# sb-mote.net
KiCad netlist of a schematic drawn in EAGLE
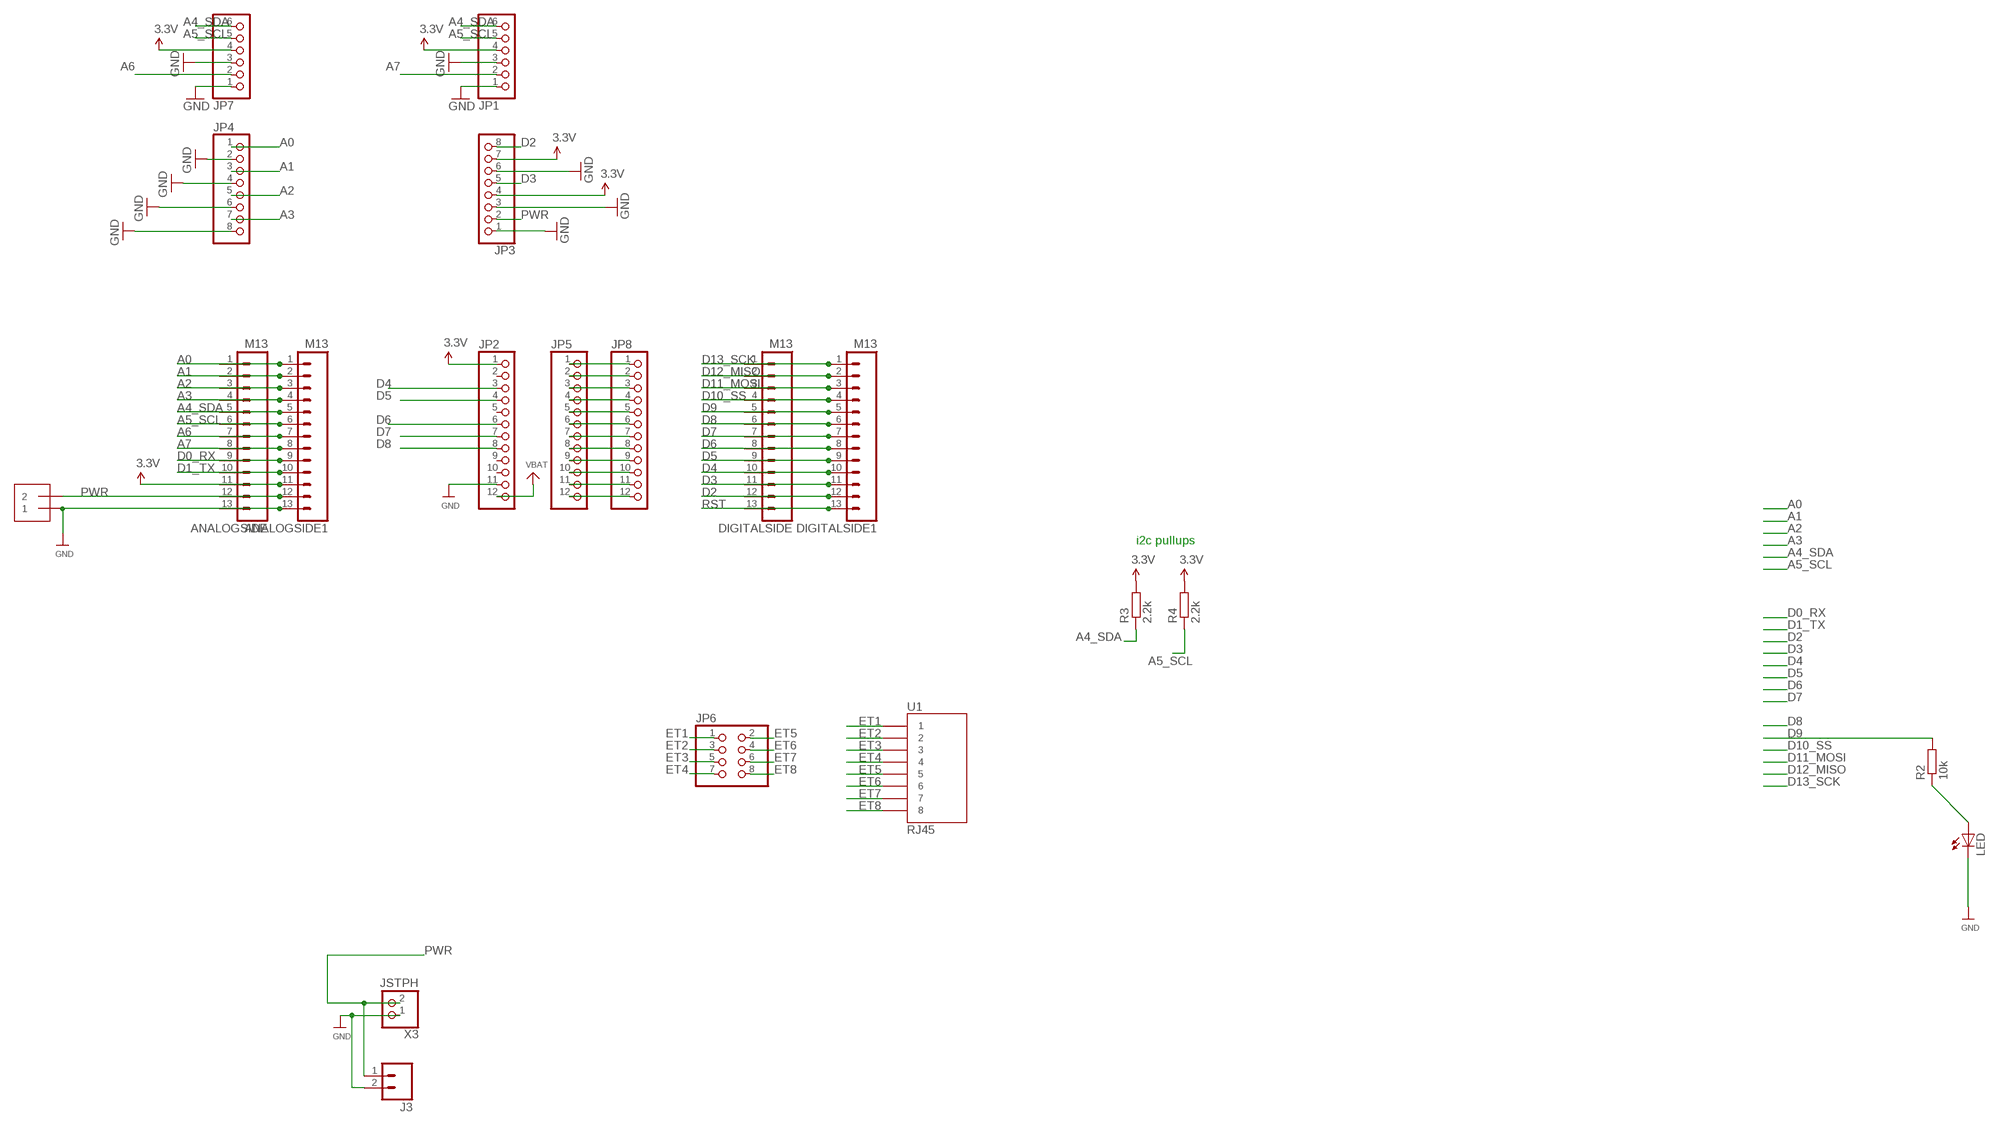
[diagram p0: schematic, sheet 1]

(export (version "E")
  (design (tool "Eeschema 10.0.6"))
  (components
    (comp (ref "ANALOGSIDE")
      (value "M13")
      (footprint "eagle-import:1X13")
      (libsource (lib "eagle-import") (part "M13"))
    )
    (comp (ref "ANALOGSIDE1")
      (value "M13")
      (footprint "eagle-import:1X13")
      (libsource (lib "eagle-import") (part "M13"))
    )
    (comp (ref "DIGITALSIDE")
      (value "M13")
      (footprint "eagle-import:1X13")
      (libsource (lib "eagle-import") (part "M13"))
    )
    (comp (ref "DIGITALSIDE1")
      (value "M13")
      (footprint "eagle-import:1X13")
      (libsource (lib "eagle-import") (part "M13"))
    )
    (comp (ref "J2")
      (value "1X2-3.5MM")
      (footprint "eagle-import:1X2-3.5MM")
      (libsource (lib "eagle-import") (part "1X2-3.5MM"))
    )
    (comp (ref "J3")
      (value "M02PTH")
      (footprint "eagle-import:1X02")
      (libsource (lib "eagle-import") (part "M02PTH"))
    )
    (comp (ref "JP1")
      (value "PINHD-1X6-3.5MM")
      (footprint "eagle-import:1X06-3.5MM")
      (libsource (lib "eagle-import") (part "PINHD-1X6-3.5MM"))
    )
    (comp (ref "JP2")
      (value "PINHD-1X12-CB")
      (footprint "eagle-import:1X12-CB")
      (libsource (lib "eagle-import") (part "PINHD-1X12-CB"))
    )
    (comp (ref "JP3")
      (value "PINHD-1X8-3.5MM")
      (footprint "eagle-import:1X08-3.5MM")
      (libsource (lib "eagle-import") (part "PINHD-1X8-3.5MM"))
    )
    (comp (ref "JP4")
      (value "PINHD-1X8-3.5MM")
      (footprint "eagle-import:1X08-3.5MM")
      (libsource (lib "eagle-import") (part "PINHD-1X8-3.5MM"))
    )
    (comp (ref "JP5")
      (value "PINHD-1X12-CB")
      (footprint "eagle-import:1X12-CB")
      (libsource (lib "eagle-import") (part "PINHD-1X12-CB"))
    )
    (comp (ref "JP6")
      (value "PINHD-2X4")
      (footprint "eagle-import:2X04")
      (libsource (lib "eagle-import") (part "PINHD-2X4"))
    )
    (comp (ref "JP7")
      (value "PINHD-1X6-3.5MM")
      (footprint "eagle-import:1X06-3.5MM")
      (libsource (lib "eagle-import") (part "PINHD-1X6-3.5MM"))
    )
    (comp (ref "JP8")
      (value "PINHD-1X12-CB")
      (footprint "eagle-import:1X12-CB")
      (libsource (lib "eagle-import") (part "PINHD-1X12-CB"))
    )
    (comp (ref "LED")
      (value "LED3MM")
      (footprint "eagle-import:LED3MM")
      (libsource (lib "eagle-import") (part "LED3MM"))
    )
    (comp (ref "R2")
      (value "10k")
      (footprint "eagle-import:0204_7")
      (libsource (lib "eagle-import") (part "R-EU_0204/7"))
    )
    (comp (ref "R3")
      (value "2.2k")
      (footprint "eagle-import:0204_7")
      (libsource (lib "eagle-import") (part "R-EU_0204/7"))
    )
    (comp (ref "R4")
      (value "2.2k")
      (footprint "eagle-import:0204_7")
      (libsource (lib "eagle-import") (part "R-EU_0204/7"))
    )
    (comp (ref "U1")
      (value "RJ45")
      (footprint "eagle-import:RJ45-8")
      (libsource (lib "eagle-import") (part "RJ45-8PTH"))
    )
    (comp (ref "X3")
      (value "JSTPH")
      (footprint "eagle-import:JSTPH2")
      (libsource (lib "eagle-import") (part "CON_JST_PH_2PIN"))
    )
  )
  (nets
    (net (code "1") (name "/A0") (class "Default")
      (node (ref "ANALOGSIDE") (pin "1") (pinfunction "1_1") (pintype "passive"))
      (node (ref "ANALOGSIDE1") (pin "1") (pinfunction "1_1") (pintype "passive"))
      (node (ref "JP4") (pin "1") (pinfunction "1_1") (pintype "passive"))
    )
    (net (code "2") (name "/A1") (class "Default")
      (node (ref "ANALOGSIDE") (pin "2") (pinfunction "2_2") (pintype "passive"))
      (node (ref "ANALOGSIDE1") (pin "2") (pinfunction "2_2") (pintype "passive"))
      (node (ref "JP4") (pin "3") (pinfunction "3_3") (pintype "passive"))
    )
    (net (code "3") (name "/A2") (class "Default")
      (node (ref "ANALOGSIDE") (pin "3") (pinfunction "3_3") (pintype "passive"))
      (node (ref "ANALOGSIDE1") (pin "3") (pinfunction "3_3") (pintype "passive"))
      (node (ref "JP4") (pin "5") (pinfunction "5_5") (pintype "passive"))
    )
    (net (code "4") (name "/A3") (class "Default")
      (node (ref "ANALOGSIDE") (pin "4") (pinfunction "4_4") (pintype "passive"))
      (node (ref "ANALOGSIDE1") (pin "4") (pinfunction "4_4") (pintype "passive"))
      (node (ref "JP4") (pin "7") (pinfunction "7_7") (pintype "passive"))
    )
    (net (code "5") (name "/A4_SDA") (class "Default")
      (node (ref "ANALOGSIDE") (pin "5") (pinfunction "5_5") (pintype "passive"))
      (node (ref "ANALOGSIDE1") (pin "5") (pinfunction "5_5") (pintype "passive"))
      (node (ref "JP1") (pin "6") (pinfunction "6_6") (pintype "passive"))
      (node (ref "JP7") (pin "6") (pinfunction "6_6") (pintype "passive"))
      (node (ref "R3") (pin "1") (pinfunction "1_1") (pintype "passive"))
    )
    (net (code "6") (name "/A5_SCL") (class "Default")
      (node (ref "ANALOGSIDE") (pin "6") (pinfunction "6_6") (pintype "passive"))
      (node (ref "ANALOGSIDE1") (pin "6") (pinfunction "6_6") (pintype "passive"))
      (node (ref "JP1") (pin "5") (pinfunction "5_5") (pintype "passive"))
      (node (ref "JP7") (pin "5") (pinfunction "5_5") (pintype "passive"))
      (node (ref "R4") (pin "1") (pinfunction "1_1") (pintype "passive"))
    )
    (net (code "7") (name "/A6") (class "Default")
      (node (ref "ANALOGSIDE") (pin "7") (pinfunction "7_7") (pintype "passive"))
      (node (ref "ANALOGSIDE1") (pin "7") (pinfunction "7_7") (pintype "passive"))
      (node (ref "JP7") (pin "2") (pinfunction "2_2") (pintype "passive"))
    )
    (net (code "8") (name "/A7") (class "Default")
      (node (ref "ANALOGSIDE") (pin "8") (pinfunction "8_8") (pintype "passive"))
      (node (ref "ANALOGSIDE1") (pin "8") (pinfunction "8_8") (pintype "passive"))
      (node (ref "JP1") (pin "2") (pinfunction "2_2") (pintype "passive"))
    )
    (net (code "9") (name "/D0_RX") (class "Default")
      (node (ref "ANALOGSIDE") (pin "9") (pinfunction "9_9") (pintype "passive"))
      (node (ref "ANALOGSIDE1") (pin "9") (pinfunction "9_9") (pintype "passive"))
    )
    (net (code "10") (name "/D1_TX") (class "Default")
      (node (ref "ANALOGSIDE") (pin "10") (pinfunction "10_10") (pintype "passive"))
      (node (ref "ANALOGSIDE1") (pin "10") (pinfunction "10_10") (pintype "passive"))
    )
    (net (code "11") (name "/D2") (class "Default")
      (node (ref "DIGITALSIDE") (pin "12") (pinfunction "12_12") (pintype "passive"))
      (node (ref "DIGITALSIDE1") (pin "12") (pinfunction "12_12") (pintype "passive"))
      (node (ref "JP3") (pin "8") (pinfunction "8_8") (pintype "passive"))
    )
    (net (code "12") (name "/D3") (class "Default")
      (node (ref "DIGITALSIDE") (pin "11") (pinfunction "11_11") (pintype "passive"))
      (node (ref "DIGITALSIDE1") (pin "11") (pinfunction "11_11") (pintype "passive"))
      (node (ref "JP3") (pin "5") (pinfunction "5_5") (pintype "passive"))
    )
    (net (code "13") (name "/D4") (class "Default")
      (node (ref "DIGITALSIDE") (pin "10") (pinfunction "10_10") (pintype "passive"))
      (node (ref "DIGITALSIDE1") (pin "10") (pinfunction "10_10") (pintype "passive"))
      (node (ref "JP2") (pin "3") (pinfunction "3_3") (pintype "passive"))
    )
    (net (code "14") (name "/D5") (class "Default")
      (node (ref "DIGITALSIDE") (pin "9") (pinfunction "9_9") (pintype "passive"))
      (node (ref "DIGITALSIDE1") (pin "9") (pinfunction "9_9") (pintype "passive"))
      (node (ref "JP2") (pin "4") (pinfunction "4_4") (pintype "passive"))
    )
    (net (code "15") (name "/D6") (class "Default")
      (node (ref "DIGITALSIDE") (pin "8") (pinfunction "8_8") (pintype "passive"))
      (node (ref "DIGITALSIDE1") (pin "8") (pinfunction "8_8") (pintype "passive"))
      (node (ref "JP2") (pin "6") (pinfunction "6_6") (pintype "passive"))
    )
    (net (code "16") (name "/D7") (class "Default")
      (node (ref "DIGITALSIDE") (pin "7") (pinfunction "7_7") (pintype "passive"))
      (node (ref "DIGITALSIDE1") (pin "7") (pinfunction "7_7") (pintype "passive"))
      (node (ref "JP2") (pin "7") (pinfunction "7_7") (pintype "passive"))
    )
    (net (code "17") (name "/D8") (class "Default")
      (node (ref "DIGITALSIDE") (pin "6") (pinfunction "6_6") (pintype "passive"))
      (node (ref "DIGITALSIDE1") (pin "6") (pinfunction "6_6") (pintype "passive"))
      (node (ref "JP2") (pin "8") (pinfunction "8_8") (pintype "passive"))
    )
    (net (code "18") (name "/D9") (class "Default")
      (node (ref "DIGITALSIDE") (pin "5") (pinfunction "5_5") (pintype "passive"))
      (node (ref "DIGITALSIDE1") (pin "5") (pinfunction "5_5") (pintype "passive"))
      (node (ref "R2") (pin "2") (pinfunction "2_2") (pintype "passive"))
    )
    (net (code "19") (name "/D10_SS") (class "Default")
      (node (ref "DIGITALSIDE") (pin "4") (pinfunction "4_4") (pintype "passive"))
      (node (ref "DIGITALSIDE1") (pin "4") (pinfunction "4_4") (pintype "passive"))
    )
    (net (code "20") (name "/D11_MOSI") (class "Default")
      (node (ref "DIGITALSIDE") (pin "3") (pinfunction "3_3") (pintype "passive"))
      (node (ref "DIGITALSIDE1") (pin "3") (pinfunction "3_3") (pintype "passive"))
    )
    (net (code "21") (name "/D12_MISO") (class "Default")
      (node (ref "DIGITALSIDE") (pin "2") (pinfunction "2_2") (pintype "passive"))
      (node (ref "DIGITALSIDE1") (pin "2") (pinfunction "2_2") (pintype "passive"))
    )
    (net (code "22") (name "/D13_SCK") (class "Default")
      (node (ref "DIGITALSIDE") (pin "1") (pinfunction "1_1") (pintype "passive"))
      (node (ref "DIGITALSIDE1") (pin "1") (pinfunction "1_1") (pintype "passive"))
    )
    (net (code "23") (name "/ET1") (class "Default")
      (node (ref "JP6") (pin "1") (pinfunction "1_1") (pintype "passive"))
      (node (ref "U1") (pin "1") (pinfunction "1_1") (pintype "bidirectional"))
    )
    (net (code "24") (name "/ET2") (class "Default")
      (node (ref "JP6") (pin "3") (pinfunction "3_3") (pintype "passive"))
      (node (ref "U1") (pin "2") (pinfunction "2_2") (pintype "bidirectional"))
    )
    (net (code "25") (name "/ET3") (class "Default")
      (node (ref "JP6") (pin "5") (pinfunction "5_5") (pintype "passive"))
      (node (ref "U1") (pin "3") (pinfunction "3_3") (pintype "bidirectional"))
    )
    (net (code "26") (name "/ET4") (class "Default")
      (node (ref "JP6") (pin "7") (pinfunction "7_7") (pintype "passive"))
      (node (ref "U1") (pin "4") (pinfunction "4_4") (pintype "bidirectional"))
    )
    (net (code "27") (name "/ET5") (class "Default")
      (node (ref "JP6") (pin "2") (pinfunction "2_2") (pintype "passive"))
      (node (ref "U1") (pin "5") (pinfunction "5_5") (pintype "bidirectional"))
    )
    (net (code "28") (name "/ET6") (class "Default")
      (node (ref "JP6") (pin "4") (pinfunction "4_4") (pintype "passive"))
      (node (ref "U1") (pin "6") (pinfunction "6_6") (pintype "bidirectional"))
    )
    (net (code "29") (name "/ET7") (class "Default")
      (node (ref "JP6") (pin "6") (pinfunction "6_6") (pintype "passive"))
      (node (ref "U1") (pin "7") (pinfunction "7_7") (pintype "bidirectional"))
    )
    (net (code "30") (name "/ET8") (class "Default")
      (node (ref "JP6") (pin "8") (pinfunction "8_8") (pintype "passive"))
      (node (ref "U1") (pin "8") (pinfunction "8_8") (pintype "bidirectional"))
    )
    (net (code "31") (name "/PWR") (class "Default")
      (node (ref "ANALOGSIDE") (pin "12") (pinfunction "12_12") (pintype "passive"))
      (node (ref "ANALOGSIDE1") (pin "12") (pinfunction "12_12") (pintype "passive"))
      (node (ref "J2") (pin "2") (pinfunction "2_2") (pintype "passive"))
      (node (ref "J3") (pin "1") (pinfunction "1_1") (pintype "passive"))
      (node (ref "JP3") (pin "2") (pinfunction "2_2") (pintype "passive"))
      (node (ref "X3") (pin "2") (pinfunction "2_2") (pintype "passive"))
    )
    (net (code "32") (name "/RST") (class "Default")
      (node (ref "DIGITALSIDE") (pin "13") (pinfunction "13_13") (pintype "passive"))
      (node (ref "DIGITALSIDE1") (pin "13") (pinfunction "13_13") (pintype "passive"))
    )
    (net (code "33") (name "3.3V") (class "Default")
      (node (ref "ANALOGSIDE") (pin "11") (pinfunction "11_11") (pintype "passive"))
      (node (ref "ANALOGSIDE1") (pin "11") (pinfunction "11_11") (pintype "passive"))
      (node (ref "JP1") (pin "4") (pinfunction "4_4") (pintype "passive"))
      (node (ref "JP2") (pin "1") (pinfunction "1_1") (pintype "passive"))
      (node (ref "JP3") (pin "4") (pinfunction "4_4") (pintype "passive"))
      (node (ref "JP3") (pin "7") (pinfunction "7_7") (pintype "passive"))
      (node (ref "JP7") (pin "4") (pinfunction "4_4") (pintype "passive"))
      (node (ref "R3") (pin "2") (pinfunction "2_2") (pintype "passive"))
      (node (ref "R4") (pin "2") (pinfunction "2_2") (pintype "passive"))
    )
    (net (code "34") (name "GND") (class "Default")
      (node (ref "ANALOGSIDE") (pin "13") (pinfunction "13_13") (pintype "passive"))
      (node (ref "ANALOGSIDE1") (pin "13") (pinfunction "13_13") (pintype "passive"))
      (node (ref "J2") (pin "1") (pinfunction "1_1") (pintype "passive"))
      (node (ref "J3") (pin "2") (pinfunction "2_2") (pintype "passive"))
      (node (ref "JP1") (pin "1") (pinfunction "1_1") (pintype "passive"))
      (node (ref "JP1") (pin "3") (pinfunction "3_3") (pintype "passive"))
      (node (ref "JP2") (pin "11") (pinfunction "11_11") (pintype "passive"))
      (node (ref "JP3") (pin "1") (pinfunction "1_1") (pintype "passive"))
      (node (ref "JP3") (pin "3") (pinfunction "3_3") (pintype "passive"))
      (node (ref "JP3") (pin "6") (pinfunction "6_6") (pintype "passive"))
      (node (ref "JP4") (pin "2") (pinfunction "2_2") (pintype "passive"))
      (node (ref "JP4") (pin "4") (pinfunction "4_4") (pintype "passive"))
      (node (ref "JP4") (pin "6") (pinfunction "6_6") (pintype "passive"))
      (node (ref "JP4") (pin "8") (pinfunction "8_8") (pintype "passive"))
      (node (ref "JP7") (pin "1") (pinfunction "1_1") (pintype "passive"))
      (node (ref "JP7") (pin "3") (pinfunction "3_3") (pintype "passive"))
      (node (ref "LED") (pin "K") (pinfunction "C_K") (pintype "passive"))
      (node (ref "X3") (pin "1") (pinfunction "1_1") (pintype "passive"))
    )
    (net (code "35") (name "Net-(JP5-Pad1)") (class "Default")
      (node (ref "JP5") (pin "1") (pinfunction "1_1") (pintype "passive"))
      (node (ref "JP8") (pin "1") (pinfunction "1_1") (pintype "passive"))
    )
    (net (code "36") (name "Net-(JP5-Pad2)") (class "Default")
      (node (ref "JP5") (pin "2") (pinfunction "2_2") (pintype "passive"))
      (node (ref "JP8") (pin "2") (pinfunction "2_2") (pintype "passive"))
    )
    (net (code "37") (name "Net-(JP5-Pad3)") (class "Default")
      (node (ref "JP5") (pin "3") (pinfunction "3_3") (pintype "passive"))
      (node (ref "JP8") (pin "3") (pinfunction "3_3") (pintype "passive"))
    )
    (net (code "38") (name "Net-(JP5-Pad4)") (class "Default")
      (node (ref "JP5") (pin "4") (pinfunction "4_4") (pintype "passive"))
      (node (ref "JP8") (pin "4") (pinfunction "4_4") (pintype "passive"))
    )
    (net (code "39") (name "Net-(JP5-Pad5)") (class "Default")
      (node (ref "JP5") (pin "5") (pinfunction "5_5") (pintype "passive"))
      (node (ref "JP8") (pin "5") (pinfunction "5_5") (pintype "passive"))
    )
    (net (code "40") (name "Net-(JP5-Pad6)") (class "Default")
      (node (ref "JP5") (pin "6") (pinfunction "6_6") (pintype "passive"))
      (node (ref "JP8") (pin "6") (pinfunction "6_6") (pintype "passive"))
    )
    (net (code "41") (name "Net-(JP5-Pad7)") (class "Default")
      (node (ref "JP5") (pin "7") (pinfunction "7_7") (pintype "passive"))
      (node (ref "JP8") (pin "7") (pinfunction "7_7") (pintype "passive"))
    )
    (net (code "42") (name "Net-(JP5-Pad8)") (class "Default")
      (node (ref "JP5") (pin "8") (pinfunction "8_8") (pintype "passive"))
      (node (ref "JP8") (pin "8") (pinfunction "8_8") (pintype "passive"))
    )
    (net (code "43") (name "Net-(JP5-Pad9)") (class "Default")
      (node (ref "JP5") (pin "9") (pinfunction "9_9") (pintype "passive"))
      (node (ref "JP8") (pin "9") (pinfunction "9_9") (pintype "passive"))
    )
    (net (code "44") (name "Net-(JP5-Pad10)") (class "Default")
      (node (ref "JP5") (pin "10") (pinfunction "10_10") (pintype "passive"))
      (node (ref "JP8") (pin "10") (pinfunction "10_10") (pintype "passive"))
    )
    (net (code "45") (name "Net-(JP5-Pad11)") (class "Default")
      (node (ref "JP5") (pin "11") (pinfunction "11_11") (pintype "passive"))
      (node (ref "JP8") (pin "11") (pinfunction "11_11") (pintype "passive"))
    )
    (net (code "46") (name "Net-(JP5-Pad12)") (class "Default")
      (node (ref "JP5") (pin "12") (pinfunction "12_12") (pintype "passive"))
      (node (ref "JP8") (pin "12") (pinfunction "12_12") (pintype "passive"))
    )
    (net (code "47") (name "Net-(LED-PadA)") (class "Default")
      (node (ref "LED") (pin "A") (pinfunction "A_A") (pintype "passive"))
      (node (ref "R2") (pin "1") (pinfunction "1_1") (pintype "passive"))
    )
    (net (code "48") (name "VBAT") (class "Default")
      (node (ref "JP2") (pin "12") (pinfunction "12_12") (pintype "passive"))
    )
    (net (code "49") (name "unconnected-(JP2-Pad2)") (class "Default")
      (node (ref "JP2") (pin "2") (pinfunction "2_2") (pintype "passive"))
    )
    (net (code "50") (name "unconnected-(JP2-Pad5)") (class "Default")
      (node (ref "JP2") (pin "5") (pinfunction "5_5") (pintype "passive"))
    )
    (net (code "51") (name "unconnected-(JP2-Pad9)") (class "Default")
      (node (ref "JP2") (pin "9") (pinfunction "9_9") (pintype "passive"))
    )
    (net (code "52") (name "unconnected-(JP2-Pad10)") (class "Default")
      (node (ref "JP2") (pin "10") (pinfunction "10_10") (pintype "passive"))
    )
  )
)
